# ch446q-breakout.net
KiCad netlist of a schematic drawn in EAGLE
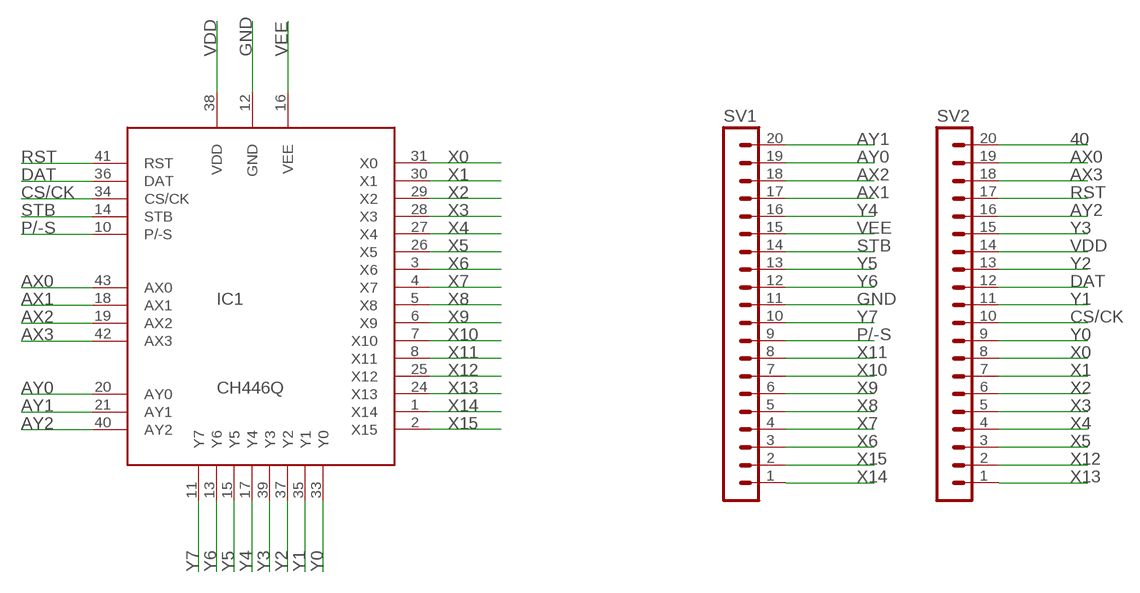
[diagram p0: schematic, sheet 1]

(export (version "E")
  (design (tool "Eeschema 10.0.6"))
  (components
    (comp (ref "IC1")
      (value "CH446Q")
      (footprint "eagle-import:LQFP-44-J")
      (libsource (lib "eagle-import") (part "CH446Q"))
    )
    (comp (ref "SV1")
      (value "MA20-1JC")
      (footprint "eagle-import:MA20-1J")
      (libsource (lib "eagle-import") (part "MA20-1JC"))
    )
    (comp (ref "SV2")
      (value "MA20-1JC")
      (footprint "eagle-import:MA20-1J")
      (libsource (lib "eagle-import") (part "MA20-1JC"))
    )
  )
  (nets
    (net (code "1") (name "/40") (class "Default")
      (node (ref "SV2") (pin "20") (pinfunction "20_20") (pintype "passive"))
    )
    (net (code "2") (name "/AX0") (class "Default")
      (node (ref "IC1") (pin "43") (pinfunction "AX0_43") (pintype "bidirectional"))
      (node (ref "SV2") (pin "19") (pinfunction "19_19") (pintype "passive"))
    )
    (net (code "3") (name "/AX1") (class "Default")
      (node (ref "IC1") (pin "18") (pinfunction "AX1_18") (pintype "bidirectional"))
      (node (ref "SV1") (pin "17") (pinfunction "17_17") (pintype "passive"))
    )
    (net (code "4") (name "/AX2") (class "Default")
      (node (ref "IC1") (pin "19") (pinfunction "AX2_19") (pintype "bidirectional"))
      (node (ref "SV1") (pin "18") (pinfunction "18_18") (pintype "passive"))
    )
    (net (code "5") (name "/AX3") (class "Default")
      (node (ref "IC1") (pin "42") (pinfunction "AX3_42") (pintype "bidirectional"))
      (node (ref "SV2") (pin "18") (pinfunction "18_18") (pintype "passive"))
    )
    (net (code "6") (name "/AY0") (class "Default")
      (node (ref "IC1") (pin "20") (pinfunction "AY0_20") (pintype "bidirectional"))
      (node (ref "SV1") (pin "19") (pinfunction "19_19") (pintype "passive"))
    )
    (net (code "7") (name "/AY1") (class "Default")
      (node (ref "IC1") (pin "21") (pinfunction "AY1_21") (pintype "bidirectional"))
      (node (ref "SV1") (pin "20") (pinfunction "20_20") (pintype "passive"))
    )
    (net (code "8") (name "/AY2") (class "Default")
      (node (ref "IC1") (pin "40") (pinfunction "AY2_40") (pintype "bidirectional"))
      (node (ref "SV2") (pin "16") (pinfunction "16_16") (pintype "passive"))
    )
    (net (code "9") (name "/CS{slash}CK") (class "Default")
      (node (ref "IC1") (pin "34") (pinfunction "CS/CK_34") (pintype "bidirectional"))
      (node (ref "SV2") (pin "10") (pinfunction "10_10") (pintype "passive"))
    )
    (net (code "10") (name "/DAT") (class "Default")
      (node (ref "IC1") (pin "36") (pinfunction "DAT_36") (pintype "bidirectional"))
      (node (ref "SV2") (pin "12") (pinfunction "12_12") (pintype "passive"))
    )
    (net (code "11") (name "/GND") (class "Default")
      (node (ref "IC1") (pin "12") (pinfunction "GND_12") (pintype "power_in"))
      (node (ref "SV1") (pin "11") (pinfunction "11_11") (pintype "passive"))
    )
    (net (code "12") (name "/P{slash}-S") (class "Default")
      (node (ref "IC1") (pin "10") (pinfunction "P/-S_10") (pintype "bidirectional"))
      (node (ref "SV1") (pin "9") (pinfunction "9_9") (pintype "passive"))
    )
    (net (code "13") (name "/RST") (class "Default")
      (node (ref "IC1") (pin "41") (pinfunction "RST_41") (pintype "bidirectional"))
      (node (ref "SV2") (pin "17") (pinfunction "17_17") (pintype "passive"))
    )
    (net (code "14") (name "/STB") (class "Default")
      (node (ref "IC1") (pin "14") (pinfunction "STB_14") (pintype "bidirectional"))
      (node (ref "SV1") (pin "14") (pinfunction "14_14") (pintype "passive"))
    )
    (net (code "15") (name "/VDD") (class "Default")
      (node (ref "IC1") (pin "38") (pinfunction "VDD_38") (pintype "power_in"))
      (node (ref "SV2") (pin "14") (pinfunction "14_14") (pintype "passive"))
    )
    (net (code "16") (name "/VEE") (class "Default")
      (node (ref "IC1") (pin "16") (pinfunction "VEE_16") (pintype "power_in"))
      (node (ref "SV1") (pin "15") (pinfunction "15_15") (pintype "passive"))
    )
    (net (code "17") (name "/X0") (class "Default")
      (node (ref "IC1") (pin "31") (pinfunction "X0_31") (pintype "bidirectional"))
      (node (ref "SV2") (pin "8") (pinfunction "8_8") (pintype "passive"))
    )
    (net (code "18") (name "/X1") (class "Default")
      (node (ref "IC1") (pin "30") (pinfunction "X1_30") (pintype "bidirectional"))
      (node (ref "SV2") (pin "7") (pinfunction "7_7") (pintype "passive"))
    )
    (net (code "19") (name "/X2") (class "Default")
      (node (ref "IC1") (pin "29") (pinfunction "X2_29") (pintype "bidirectional"))
      (node (ref "SV2") (pin "6") (pinfunction "6_6") (pintype "passive"))
    )
    (net (code "20") (name "/X3") (class "Default")
      (node (ref "IC1") (pin "28") (pinfunction "X3_28") (pintype "bidirectional"))
      (node (ref "SV2") (pin "5") (pinfunction "5_5") (pintype "passive"))
    )
    (net (code "21") (name "/X4") (class "Default")
      (node (ref "IC1") (pin "27") (pinfunction "X4_27") (pintype "bidirectional"))
      (node (ref "SV2") (pin "4") (pinfunction "4_4") (pintype "passive"))
    )
    (net (code "22") (name "/X5") (class "Default")
      (node (ref "IC1") (pin "26") (pinfunction "X5_26") (pintype "bidirectional"))
      (node (ref "SV2") (pin "3") (pinfunction "3_3") (pintype "passive"))
    )
    (net (code "23") (name "/X6") (class "Default")
      (node (ref "IC1") (pin "3") (pinfunction "X6_3") (pintype "bidirectional"))
      (node (ref "SV1") (pin "3") (pinfunction "3_3") (pintype "passive"))
    )
    (net (code "24") (name "/X7") (class "Default")
      (node (ref "IC1") (pin "4") (pinfunction "X7_4") (pintype "bidirectional"))
      (node (ref "SV1") (pin "4") (pinfunction "4_4") (pintype "passive"))
    )
    (net (code "25") (name "/X8") (class "Default")
      (node (ref "IC1") (pin "5") (pinfunction "X8_5") (pintype "bidirectional"))
      (node (ref "SV1") (pin "5") (pinfunction "5_5") (pintype "passive"))
    )
    (net (code "26") (name "/X9") (class "Default")
      (node (ref "IC1") (pin "6") (pinfunction "X9_6") (pintype "bidirectional"))
      (node (ref "SV1") (pin "6") (pinfunction "6_6") (pintype "passive"))
    )
    (net (code "27") (name "/X10") (class "Default")
      (node (ref "IC1") (pin "7") (pinfunction "X10_7") (pintype "bidirectional"))
      (node (ref "SV1") (pin "7") (pinfunction "7_7") (pintype "passive"))
    )
    (net (code "28") (name "/X11") (class "Default")
      (node (ref "IC1") (pin "8") (pinfunction "X11_8") (pintype "bidirectional"))
      (node (ref "SV1") (pin "8") (pinfunction "8_8") (pintype "passive"))
    )
    (net (code "29") (name "/X12") (class "Default")
      (node (ref "IC1") (pin "25") (pinfunction "X12_25") (pintype "bidirectional"))
      (node (ref "SV2") (pin "2") (pinfunction "2_2") (pintype "passive"))
    )
    (net (code "30") (name "/X13") (class "Default")
      (node (ref "IC1") (pin "24") (pinfunction "X13_24") (pintype "bidirectional"))
      (node (ref "SV2") (pin "1") (pinfunction "1_1") (pintype "passive"))
    )
    (net (code "31") (name "/X14") (class "Default")
      (node (ref "IC1") (pin "1") (pinfunction "X14_1") (pintype "bidirectional"))
      (node (ref "SV1") (pin "1") (pinfunction "1_1") (pintype "passive"))
    )
    (net (code "32") (name "/X15") (class "Default")
      (node (ref "IC1") (pin "2") (pinfunction "X15_2") (pintype "bidirectional"))
      (node (ref "SV1") (pin "2") (pinfunction "2_2") (pintype "passive"))
    )
    (net (code "33") (name "/Y0") (class "Default")
      (node (ref "IC1") (pin "33") (pinfunction "Y0_33") (pintype "bidirectional"))
      (node (ref "SV2") (pin "9") (pinfunction "9_9") (pintype "passive"))
    )
    (net (code "34") (name "/Y1") (class "Default")
      (node (ref "IC1") (pin "35") (pinfunction "Y1_35") (pintype "bidirectional"))
      (node (ref "SV2") (pin "11") (pinfunction "11_11") (pintype "passive"))
    )
    (net (code "35") (name "/Y2") (class "Default")
      (node (ref "IC1") (pin "37") (pinfunction "Y2_37") (pintype "bidirectional"))
      (node (ref "SV2") (pin "13") (pinfunction "13_13") (pintype "passive"))
    )
    (net (code "36") (name "/Y3") (class "Default")
      (node (ref "IC1") (pin "39") (pinfunction "Y3_39") (pintype "bidirectional"))
      (node (ref "SV2") (pin "15") (pinfunction "15_15") (pintype "passive"))
    )
    (net (code "37") (name "/Y4") (class "Default")
      (node (ref "IC1") (pin "17") (pinfunction "Y4_17") (pintype "bidirectional"))
      (node (ref "SV1") (pin "16") (pinfunction "16_16") (pintype "passive"))
    )
    (net (code "38") (name "/Y5") (class "Default")
      (node (ref "IC1") (pin "15") (pinfunction "Y5_15") (pintype "bidirectional"))
      (node (ref "SV1") (pin "13") (pinfunction "13_13") (pintype "passive"))
    )
    (net (code "39") (name "/Y6") (class "Default")
      (node (ref "IC1") (pin "13") (pinfunction "Y6_13") (pintype "bidirectional"))
      (node (ref "SV1") (pin "12") (pinfunction "12_12") (pintype "passive"))
    )
    (net (code "40") (name "/Y7") (class "Default")
      (node (ref "IC1") (pin "11") (pinfunction "Y7_11") (pintype "bidirectional"))
      (node (ref "SV1") (pin "10") (pinfunction "10_10") (pintype "passive"))
    )
  )
)
